# nixie-tube-power.net
KiCad netlist of a schematic drawn in Altium Designer
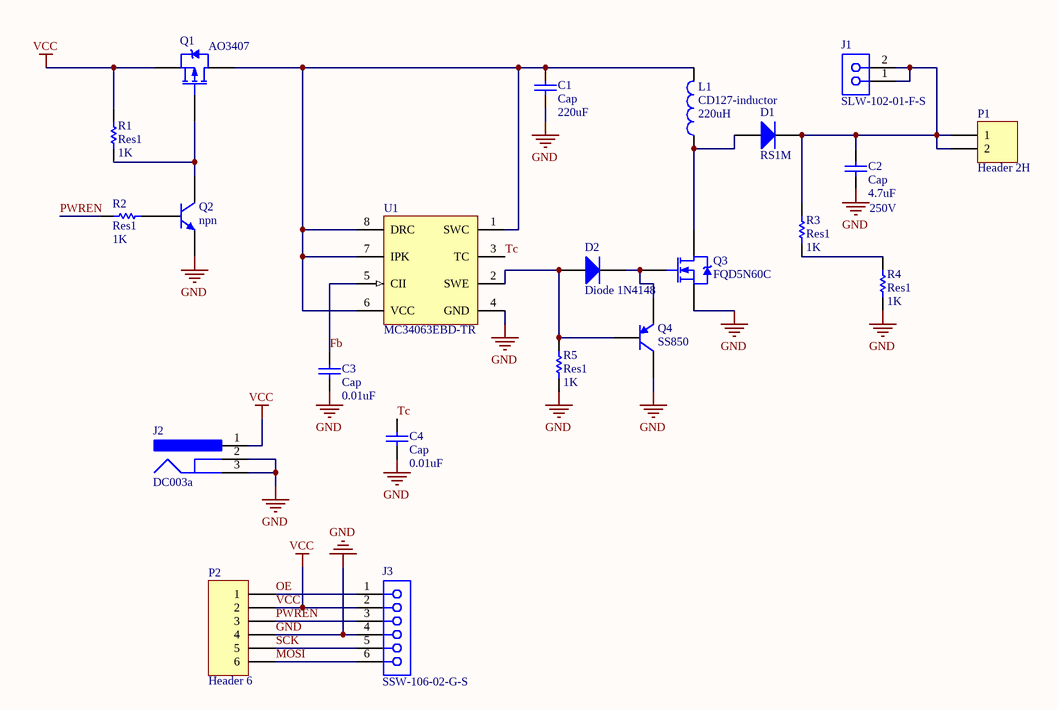
[diagram p0: nixie-tube-power.SchDoc]

(export (version "E")
  (design (tool "Eeschema 10.0.6"))
  (components
    (comp (ref "C1")
      (value "Cap")
      (footprint "220uF-35V-smd")
      (description "Capacitor")
      (fields (field (name "ALTIUM_VALUE") "220uF") (field (name "PUBLISHER") "Altium Limited"))
      (libsource (lib "Miscellaneous Devices") (part "Cap"))
    )
    (comp (ref "C2")
      (value "Cap")
      (footprint "RB5-10.5")
      (description "Capacitor")
      (fields
        (field (name "ALTIUM_VALUE") "4.7uF")
        (field (name "VOLTAGE") "250V")
        (field (name "PUBLISHER") "Altium Limited")
      )
      (libsource (lib "Miscellaneous Devices") (part "Cap"))
    )
    (comp (ref "C3")
      (value "Cap")
      (footprint "1608[0603]")
      (description "Capacitor")
      (fields (field (name "ALTIUM_VALUE") "0.01uF") (field (name "PUBLISHER") "Altium Limited"))
      (libsource (lib "Miscellaneous Devices") (part "Cap"))
    )
    (comp (ref "C4")
      (value "Cap")
      (footprint "1608[0603]")
      (description "Capacitor")
      (fields (field (name "ALTIUM_VALUE") "0.01uF") (field (name "PUBLISHER") "Altium Limited"))
      (libsource (lib "Miscellaneous Devices") (part "Cap"))
    )
    (comp (ref "D1")
      (value "RS1M")
      (footprint "DIOD-SMA-2_A_V")
      (description "Ultra-Fast Rectifier, 1 A, 1.7 V, -65 to 150 degC, 2-Pin SMD, RoHS, Tape and Reel")
      (fields (field (name "MANUFACTURER") "Diodes Inc"))
      (libsource (lib "altium-import") (part "root_0_D-AK-2_"))
    )
    (comp (ref "D2")
      (value "Diode 1N4148")
      (footprint "SODFL350X110-2N")
      (description "High Conductance Fast Diode")
      (fields (field (name "PUBLISHER") "Altium Limited"))
      (libsource (lib "Miscellaneous Devices") (part "Diode 1N4148"))
    )
    (comp (ref "J1")
      (value "SLW-102-01-F-S")
      (footprint "SMTC-SLW-102-01-X-S")
      (fields (field (name "MANUFACTURER") "Samtec"))
      (libsource (lib "altium-import") (part "root_1_SMTC-SLW-102-01-X-S_"))
    )
    (comp (ref "J2")
      (value "DC003a")
      (footprint "nixie-tube:dc003a")
      (fields (field (name "MANUFACTURER") "CUIInc."))
      (libsource (lib "altium-import") (part "root_0_JACK-2CD3-RN_"))
    )
    (comp (ref "J3")
      (value "SSW-106-02-G-S")
      (footprint "SMTC-SSW-106-02-X-S")
      (description "SQ Post Socket, Through-hole, Vertical, -55 to 125 degC, 2.54mm Pitch, 6-Pin, Female, RoHS")
      (fields (field (name "MANUFACTURER") "Samtec"))
      (libsource (lib "Altium Content Vault") (part "SMTC-SSW-106-02-X-S-X"))
    )
    (comp (ref "L1")
      (value "CD127-inductor")
      (footprint "cd127-220uH")
      (description "Inductor")
      (fields (field (name "ALTIUM_VALUE") "220uH") (field (name "PUBLISHER") "Altium Limited"))
      (libsource (lib "Miscellaneous Devices") (part "Inductor"))
    )
    (comp (ref "P1")
      (value "Header 2H")
      (footprint "HDR1X2H")
      (description "Header, 2-Pin, Right Angle")
      (fields (field (name "PUBLISHER") "Altium Limited"))
      (libsource (lib "Miscellaneous Connectors") (part "Header 2H"))
    )
    (comp (ref "P2")
      (value "Header 6")
      (footprint "HDR1X6")
      (description "Header, 6-Pin")
      (fields (field (name "PUBLISHER") "Altium Limited"))
      (libsource (lib "Miscellaneous Connectors") (part "Header 6"))
    )
    (comp (ref "Q1")
      (value "AO3407")
      (footprint "SOT23_M")
      (description "P-Channel Power MOSFET")
      (fields (field (name "PUBLISHER") "Altium Limited"))
      (libsource (lib "Miscellaneous Devices") (part "PMOS-2"))
    )
    (comp (ref "Q2")
      (value "npn")
      (footprint "SOT-23_M")
      (description "NPN General Purpose Amplifier")
      (fields (field (name "PUBLISHER") "Altium Limited"))
      (libsource (lib "Miscellaneous Devices") (part "2N3904"))
    )
    (comp (ref "Q3")
      (value "FQD5N60C")
      (footprint "SC_TO-252AA")
      (description "N-Channel Power MOSFET")
      (fields (field (name "PUBLISHER") "Altium Limited"))
      (libsource (lib "Miscellaneous Devices") (part "NMOS-2"))
    )
    (comp (ref "Q4")
      (value "SS850")
      (footprint "SOT-23_M")
      (description "PNP General Purpose Amplifier")
      (fields (field (name "PUBLISHER") "Altium Limited"))
      (libsource (lib "Miscellaneous Devices") (part "2N3906"))
    )
    (comp (ref "R1")
      (value "Res1")
      (footprint "J1-0603")
      (description "Resistor")
      (fields (field (name "ALTIUM_VALUE") "1K") (field (name "PUBLISHER") "Altium Limited"))
      (libsource (lib "Miscellaneous Devices") (part "Res1"))
    )
    (comp (ref "R2")
      (value "Res1")
      (footprint "J1-0603")
      (description "Resistor")
      (fields (field (name "ALTIUM_VALUE") "1K") (field (name "PUBLISHER") "Altium Limited"))
      (libsource (lib "Miscellaneous Devices") (part "Res1"))
    )
    (comp (ref "R3")
      (value "Res1")
      (footprint "J1-0603")
      (description "Resistor")
      (fields (field (name "ALTIUM_VALUE") "1K") (field (name "PUBLISHER") "Altium Limited"))
      (libsource (lib "Miscellaneous Devices") (part "Res1"))
    )
    (comp (ref "R4")
      (value "Res1")
      (footprint "J1-0603")
      (description "Resistor")
      (fields (field (name "ALTIUM_VALUE") "1K") (field (name "PUBLISHER") "Altium Limited"))
      (libsource (lib "Miscellaneous Devices") (part "Res1"))
    )
    (comp (ref "R5")
      (value "Res1")
      (footprint "J1-0603")
      (description "Resistor")
      (fields (field (name "ALTIUM_VALUE") "1K") (field (name "PUBLISHER") "Altium Limited"))
      (libsource (lib "Miscellaneous Devices") (part "Res1"))
    )
    (comp (ref "U1")
      (value "MC34063EBD-TR")
      (footprint "SO8_M")
      (description "DC/DC converter control circuit, 8-Pin SO, Tape and Reel")
      (libsource (lib "altium-import") (part "root_0_PM-SWREG-MC34063-IL8_"))
    )
  )
  (nets
    (net (code "1") (name "/Fb") (class "Default")
      (node (ref "C3") (pin "2") (pinfunction "2_2") (pintype "passive"))
      (node (ref "U1") (pin "5") (pinfunction "CII_5") (pintype "input"))
    )
    (net (code "2") (name "/MOSI") (class "Default")
      (node (ref "J3") (pin "6") (pinfunction "6_6") (pintype "passive"))
      (node (ref "P2") (pin "6") (pinfunction "6_6") (pintype "passive"))
    )
    (net (code "3") (name "/OE") (class "Default")
      (node (ref "J3") (pin "1") (pinfunction "1_1") (pintype "passive"))
      (node (ref "P2") (pin "1") (pinfunction "1_1") (pintype "passive"))
    )
    (net (code "4") (name "/PWREN") (class "Default")
      (node (ref "J3") (pin "3") (pinfunction "3_3") (pintype "passive"))
      (node (ref "P2") (pin "3") (pinfunction "3_3") (pintype "passive"))
      (node (ref "R2") (pin "2") (pinfunction "2_2") (pintype "passive"))
    )
    (net (code "5") (name "/SCK") (class "Default")
      (node (ref "J3") (pin "5") (pinfunction "5_5") (pintype "passive"))
      (node (ref "P2") (pin "5") (pinfunction "5_5") (pintype "passive"))
    )
    (net (code "6") (name "/Tc") (class "Default")
      (node (ref "C4") (pin "2") (pinfunction "2_2") (pintype "passive"))
      (node (ref "U1") (pin "3") (pinfunction "TC_3") (pintype "passive"))
    )
    (net (code "7") (name "GND") (class "Default")
      (node (ref "C1") (pin "1") (pinfunction "1_1") (pintype "passive"))
      (node (ref "C2") (pin "1") (pinfunction "1_1") (pintype "passive"))
      (node (ref "C3") (pin "1") (pinfunction "1_1") (pintype "passive"))
      (node (ref "C4") (pin "1") (pinfunction "1_1") (pintype "passive"))
      (node (ref "J2") (pin "2") (pinfunction "2_2") (pintype "passive"))
      (node (ref "J2") (pin "3") (pinfunction "3_3") (pintype "passive"))
      (node (ref "J3") (pin "4") (pinfunction "4_4") (pintype "passive"))
      (node (ref "P2") (pin "4") (pinfunction "4_4") (pintype "passive"))
      (node (ref "Q2") (pin "1") (pinfunction "E_1") (pintype "passive"))
      (node (ref "Q3") (pin "3") (pinfunction "S_3") (pintype "passive"))
      (node (ref "Q4") (pin "3") (pinfunction "C_3") (pintype "passive"))
      (node (ref "R4") (pin "1") (pinfunction "1_1") (pintype "passive"))
      (node (ref "R5") (pin "1") (pinfunction "1_1") (pintype "passive"))
      (node (ref "U1") (pin "4") (pinfunction "GND_4") (pintype "power_in"))
    )
    (net (code "8") (name "Net-(D1-A)") (class "Default")
      (node (ref "D1") (pin "1") (pinfunction "A_1") (pintype "passive"))
      (node (ref "L1") (pin "1") (pinfunction "1_1") (pintype "passive"))
      (node (ref "Q3") (pin "2") (pinfunction "D_2") (pintype "passive"))
    )
    (net (code "9") (name "Net-(D1-K)") (class "Default")
      (node (ref "C2") (pin "2") (pinfunction "2_2") (pintype "passive"))
      (node (ref "D1") (pin "2") (pinfunction "K_2") (pintype "passive"))
      (node (ref "J1") (pin "1") (pinfunction "1_1") (pintype "passive"))
      (node (ref "J1") (pin "2") (pinfunction "2_2") (pintype "passive"))
      (node (ref "P1") (pin "1") (pinfunction "1_1") (pintype "passive"))
      (node (ref "P1") (pin "2") (pinfunction "2_2") (pintype "passive"))
      (node (ref "R3") (pin "2") (pinfunction "2_2") (pintype "passive"))
    )
    (net (code "10") (name "Net-(D2-A)") (class "Default")
      (node (ref "D2") (pin "1") (pinfunction "A_1") (pintype "passive"))
      (node (ref "Q4") (pin "2") (pinfunction "B_2") (pintype "passive"))
      (node (ref "R5") (pin "2") (pinfunction "2_2") (pintype "passive"))
      (node (ref "U1") (pin "2") (pinfunction "SWE_2") (pintype "open_emitter"))
    )
    (net (code "11") (name "Net-(D2-K)") (class "Default")
      (node (ref "D2") (pin "2") (pinfunction "K_2") (pintype "passive"))
      (node (ref "Q3") (pin "1") (pinfunction "G_1") (pintype "passive"))
      (node (ref "Q4") (pin "1") (pinfunction "E_1") (pintype "passive"))
    )
    (net (code "12") (name "Net-(Q1-D)") (class "Default")
      (node (ref "C1") (pin "2") (pinfunction "2_2") (pintype "passive"))
      (node (ref "L1") (pin "2") (pinfunction "2_2") (pintype "passive"))
      (node (ref "Q1") (pin "2") (pinfunction "D_2") (pintype "passive"))
      (node (ref "U1") (pin "1") (pinfunction "SWC_1") (pintype "open_collector"))
      (node (ref "U1") (pin "6") (pinfunction "VCC_6") (pintype "power_in"))
      (node (ref "U1") (pin "7") (pinfunction "IPK_7") (pintype "passive"))
      (node (ref "U1") (pin "8") (pinfunction "DRC_8") (pintype "open_collector"))
    )
    (net (code "13") (name "Net-(Q1-G)") (class "Default")
      (node (ref "Q1") (pin "1") (pinfunction "G_1") (pintype "passive"))
      (node (ref "Q2") (pin "3") (pinfunction "C_3") (pintype "passive"))
      (node (ref "R1") (pin "1") (pinfunction "1_1") (pintype "passive"))
    )
    (net (code "14") (name "Net-(Q2-B)") (class "Default")
      (node (ref "Q2") (pin "2") (pinfunction "B_2") (pintype "passive"))
      (node (ref "R2") (pin "1") (pinfunction "1_1") (pintype "passive"))
    )
    (net (code "15") (name "Net-(R3-Pad1)") (class "Default")
      (node (ref "R3") (pin "1") (pinfunction "1_1") (pintype "passive"))
      (node (ref "R4") (pin "2") (pinfunction "2_2") (pintype "passive"))
    )
    (net (code "16") (name "VCC") (class "Default")
      (node (ref "J2") (pin "1") (pinfunction "1_1") (pintype "passive"))
      (node (ref "J3") (pin "2") (pinfunction "2_2") (pintype "passive"))
      (node (ref "P2") (pin "2") (pinfunction "2_2") (pintype "passive"))
      (node (ref "Q1") (pin "3") (pinfunction "S_3") (pintype "passive"))
      (node (ref "R1") (pin "2") (pinfunction "2_2") (pintype "passive"))
    )
  )
)
